# TSL2591_breakout.net
KiCad netlist of a schematic drawn in EAGLE
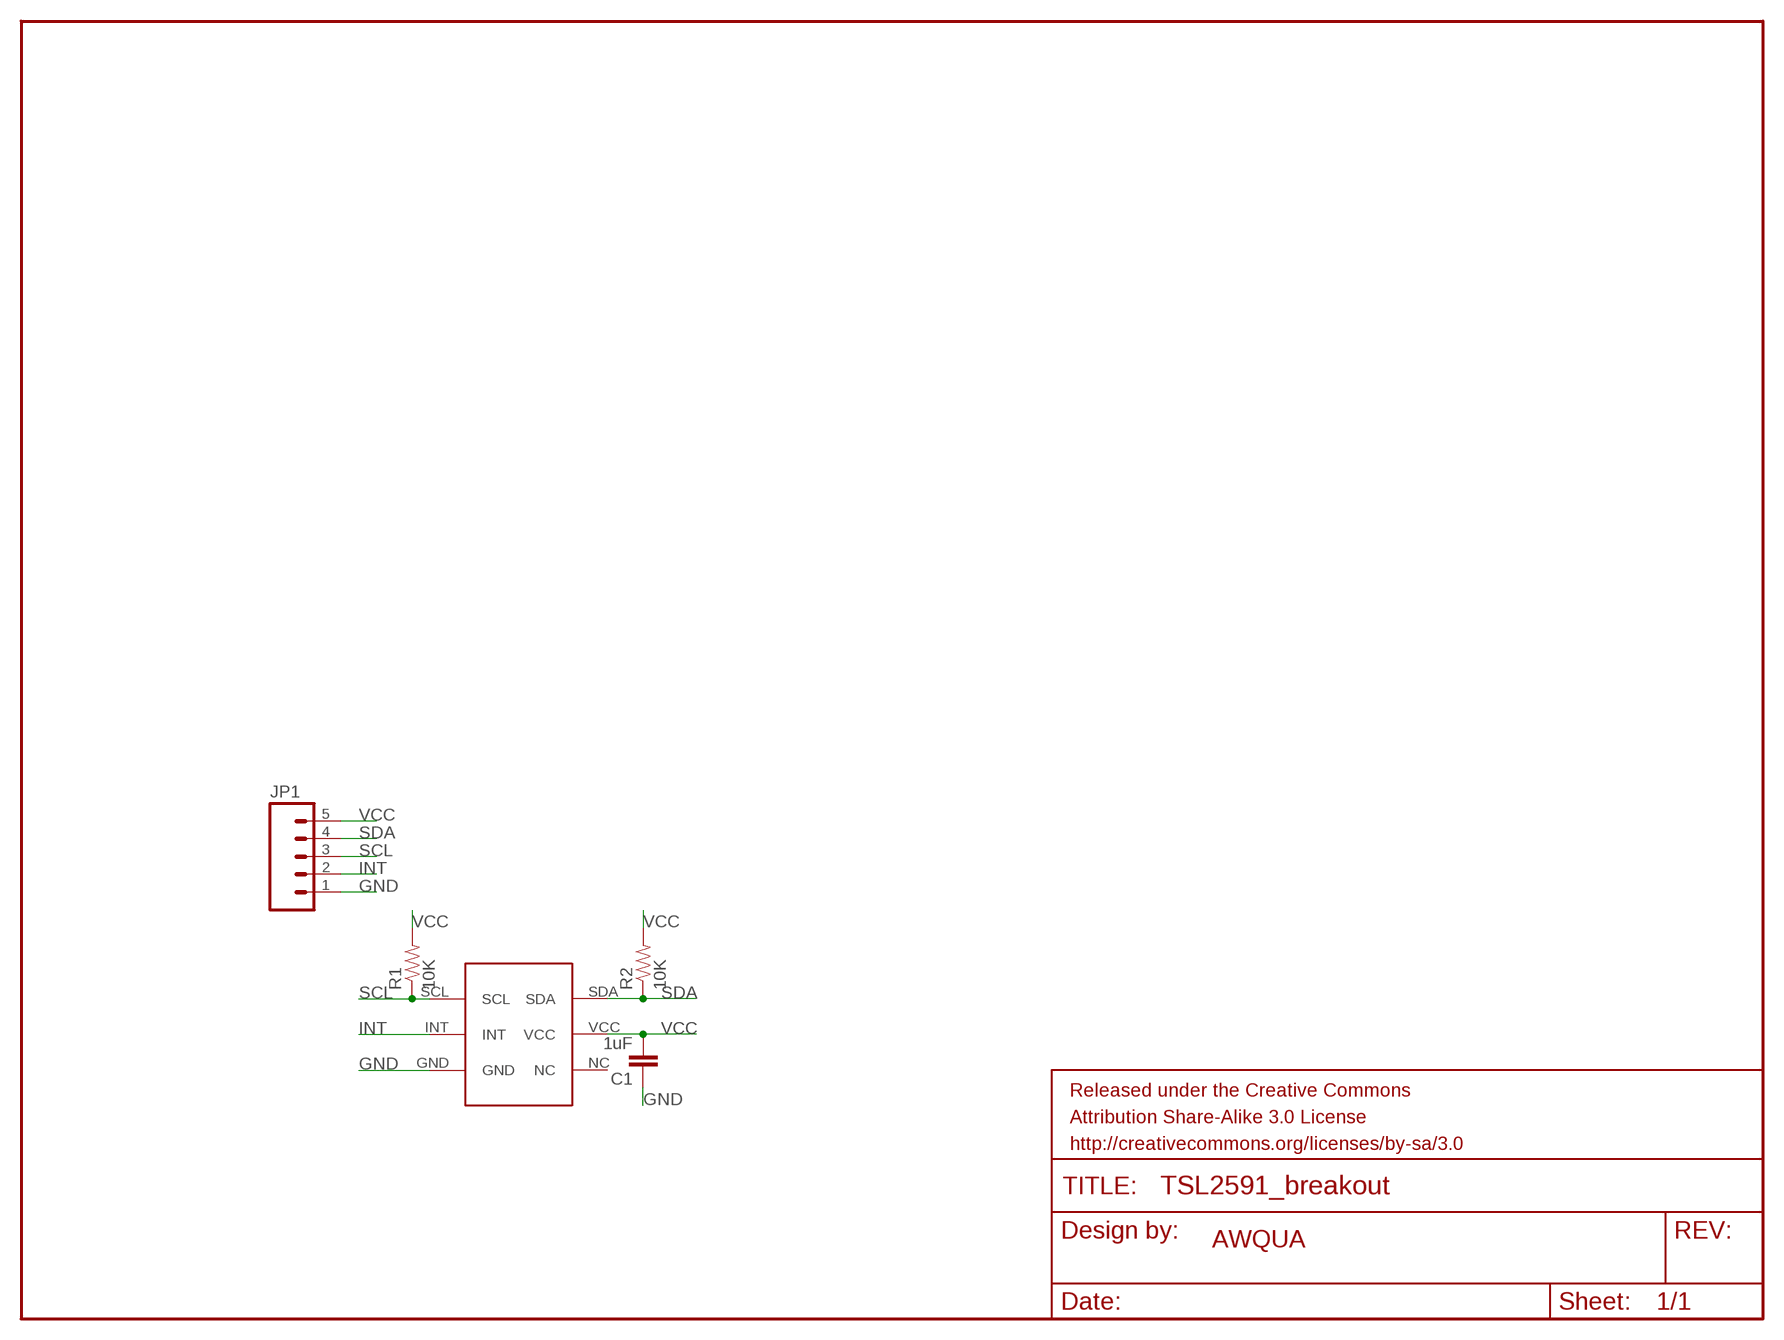
[diagram p0: schematic, sheet 1]

(export (version "E")
  (design (tool "Eeschema 10.0.6"))
  (components
    (comp (ref "C1")
      (value "1uF")
      (footprint "eagle-import:0603-CAP")
      (libsource (lib "eagle-import") (part "CAP0603-CAP"))
    )
    (comp (ref "FRAME1")
      (value "FRAME-LETTER")
      (footprint "eagle-import:CREATIVE_COMMONS")
      (libsource (lib "eagle-import") (part "FRAME-LETTER"))
    )
    (comp (ref "JP1")
      (value "M05NO_SILK")
      (footprint "eagle-import:1X05_NO_SILK")
      (libsource (lib "eagle-import") (part "M05NO_SILK"))
    )
    (comp (ref "R1")
      (value "10K")
      (footprint "eagle-import:0603-RES")
      (libsource (lib "eagle-import") (part "RESISTOR0603-RES"))
    )
    (comp (ref "R2")
      (value "10K")
      (footprint "eagle-import:0603-RES")
      (libsource (lib "eagle-import") (part "RESISTOR0603-RES"))
    )
    (comp (ref "U$1")
      (value "TSL2591")
      (footprint "eagle-import:TSL2591")
      (libsource (lib "eagle-import") (part "TSL2591"))
    )
  )
  (nets
    (net (code "1") (name "/GND") (class "Default")
      (node (ref "C1") (pin "1") (pinfunction "1_1") (pintype "passive"))
      (node (ref "JP1") (pin "1") (pinfunction "1_1") (pintype "passive"))
      (node (ref "U$1") (pin "GND") (pinfunction "GND_GND") (pintype "bidirectional"))
    )
    (net (code "2") (name "/INT") (class "Default")
      (node (ref "JP1") (pin "2") (pinfunction "2_2") (pintype "passive"))
      (node (ref "U$1") (pin "INT") (pinfunction "INT_INT") (pintype "bidirectional"))
    )
    (net (code "3") (name "/SCL") (class "Default")
      (node (ref "JP1") (pin "3") (pinfunction "3_3") (pintype "passive"))
      (node (ref "R1") (pin "1") (pinfunction "1_1") (pintype "passive"))
      (node (ref "U$1") (pin "SCL") (pinfunction "SCL_SCL") (pintype "bidirectional"))
    )
    (net (code "4") (name "/SDA") (class "Default")
      (node (ref "JP1") (pin "4") (pinfunction "4_4") (pintype "passive"))
      (node (ref "R2") (pin "1") (pinfunction "1_1") (pintype "passive"))
      (node (ref "U$1") (pin "SDA") (pinfunction "SDA_SDA") (pintype "bidirectional"))
    )
    (net (code "5") (name "/VCC") (class "Default")
      (node (ref "C1") (pin "2") (pinfunction "2_2") (pintype "passive"))
      (node (ref "JP1") (pin "5") (pinfunction "5_5") (pintype "passive"))
      (node (ref "R1") (pin "2") (pinfunction "2_2") (pintype "passive"))
      (node (ref "R2") (pin "2") (pinfunction "2_2") (pintype "passive"))
      (node (ref "U$1") (pin "VCC") (pinfunction "VCC_VCC") (pintype "bidirectional"))
    )
    (net (code "6") (name "unconnected-(U$1-PadNC)") (class "Default")
      (node (ref "U$1") (pin "NC") (pinfunction "NC_NC") (pintype "bidirectional"))
    )
  )
)
